# Display_Segmental_LCD118x1_DF700543-05_B.net
KiCad netlist of a schematic drawn in Altium Designer
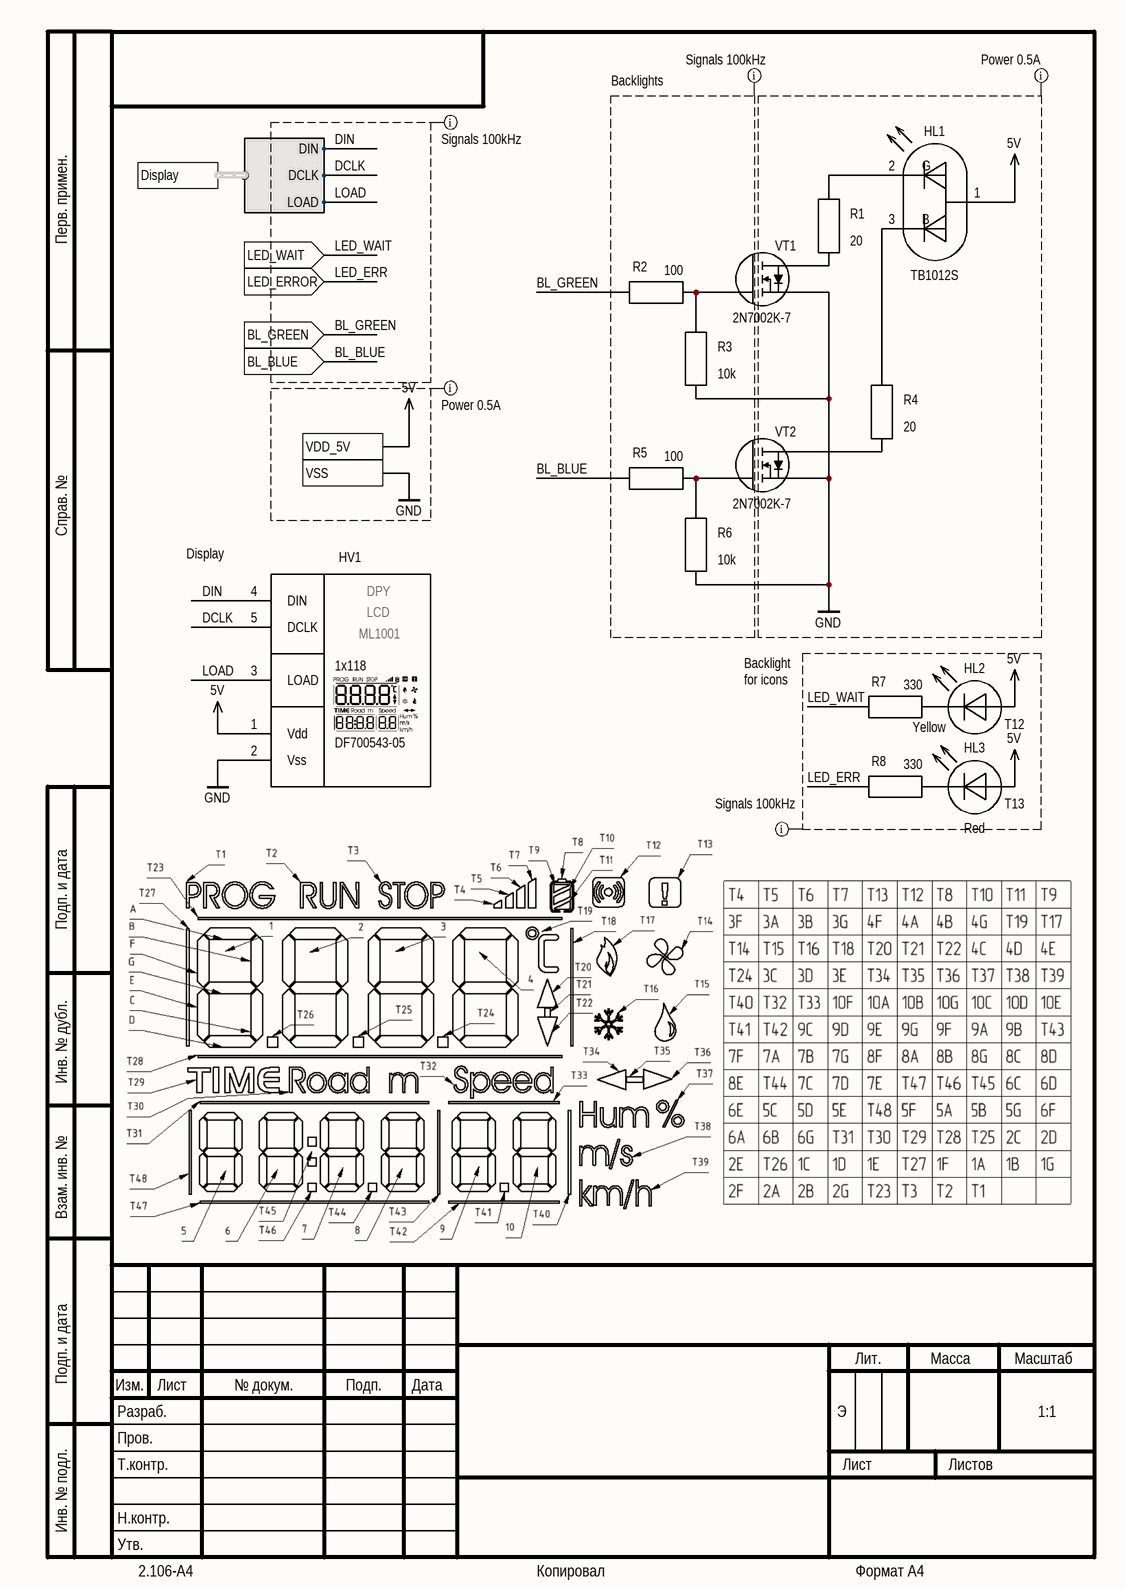
[diagram p0: Display Segmental LCD118x1 DF700543-05 Backlight TB1012S 1608.SchDoc]

(export (version "E")
  (design (tool "Eeschema 10.0.6"))
  (components
    (comp (ref "HL1")
      (value "TB1012S")
      (footprint "DISP BKL LED TB1012S")
      (description "Display Backlight LED GB CA")
      (libsource (lib "Displays") (part "TB1012S"))
    )
    (comp (ref "HL2")
      (value "Yellow")
      (footprint "LEDD3TBN")
      (description "LED Yellow TH D3mm")
      (fields (field (name "MANUFACTURER") "Lite-On"))
      (libsource (lib "LED") (part "LTL-4251"))
    )
    (comp (ref "HL3")
      (value "Red")
      (footprint "LEDD3TBN")
      (description "LED Red TH D3mm")
      (fields (field (name "MANUFACTURER") "Lite-On"))
      (libsource (lib "LED") (part "LTL-4211"))
    )
    (comp (ref "HV1")
      (value "DF700543-05")
      (footprint "DISP SEG LCD128 DF700543-05")
      (description "Display Segmental LCD128 Special")
      (libsource (lib "Displays") (part "DF700543-05"))
    )
    (comp (ref "R1")
      (value "20")
      (footprint "RESC3225N")
      (description "RESC 20 1210(3225)")
      (fields (field (name "MANUFACTURER") "Yageo") (field (name "TOLERANCE") "±1%"))
      (libsource (lib "Resistors Ceramic SMD") (part "RC1210JR-0720RL"))
    )
    (comp (ref "R2")
      (value "100")
      (footprint "RESC1608N")
      (description "RESC 100 0603(1608)")
      (fields (field (name "MANUFACTURER") "Yageo") (field (name "TOLERANCE") "±5%"))
      (libsource (lib "Resistors Ceramic SMD") (part "RC0603JR-07100RL"))
    )
    (comp (ref "R3")
      (value "10k")
      (footprint "RESC1608N")
      (description "RESC 10k 0603(1608)")
      (fields (field (name "MANUFACTURER") "Yageo") (field (name "TOLERANCE") "±5%"))
      (libsource (lib "Resistors Ceramic SMD") (part "RC0603JR-0710KL"))
    )
    (comp (ref "R4")
      (value "20")
      (footprint "RESC3225N")
      (description "RESC 20 1210(3225)")
      (fields (field (name "MANUFACTURER") "Yageo") (field (name "TOLERANCE") "±1%"))
      (libsource (lib "Resistors Ceramic SMD") (part "RC1210JR-0720RL"))
    )
    (comp (ref "R5")
      (value "100")
      (footprint "RESC1608N")
      (description "RESC 100 0603(1608)")
      (fields (field (name "MANUFACTURER") "Yageo") (field (name "TOLERANCE") "±5%"))
      (libsource (lib "Resistors Ceramic SMD") (part "RC0603JR-07100RL"))
    )
    (comp (ref "R6")
      (value "10k")
      (footprint "RESC1608N")
      (description "RESC 10k 0603(1608)")
      (fields (field (name "MANUFACTURER") "Yageo") (field (name "TOLERANCE") "±5%"))
      (libsource (lib "Resistors Ceramic SMD") (part "RC0603JR-0710KL"))
    )
    (comp (ref "R7")
      (value "330")
      (footprint "RESC1608N")
      (description "RESC 330 0603(1608)")
      (fields (field (name "MANUFACTURER") "Yageo") (field (name "TOLERANCE") "±5%"))
      (libsource (lib "Resistors Ceramic SMD") (part "RC0603JR-07330RL"))
    )
    (comp (ref "R8")
      (value "330")
      (footprint "RESC1608N")
      (description "RESC 330 0603(1608)")
      (fields (field (name "MANUFACTURER") "Yageo") (field (name "TOLERANCE") "±5%"))
      (libsource (lib "Resistors Ceramic SMD") (part "RC0603JR-07330RL"))
    )
    (comp (ref "VT1")
      (value "2N7002K-7")
      (footprint "SOT-23-3N")
      (description "MOSFET N 0.38A 60V")
      (fields (field (name "MANUFACTURER") "Diodes Incorporated"))
      (libsource (lib "Transistors") (part "2N7002K-7"))
    )
    (comp (ref "VT2")
      (value "2N7002K-7")
      (footprint "SOT-23-3N")
      (description "MOSFET N 0.38A 60V")
      (fields (field (name "MANUFACTURER") "Diodes Incorporated"))
      (libsource (lib "Transistors") (part "2N7002K-7"))
    )
  )
  (nets
    (net (code "2") (name "/BL_BLUE") (class "Default")
      (node (ref "R5") (pin "1") (pinfunction "1_1") (pintype "passive"))
    )
    (net (code "3") (name "/BL_GREEN") (class "Default")
      (node (ref "R2") (pin "1") (pinfunction "1_1") (pintype "passive"))
    )
    (net (code "4") (name "/DCLK") (class "Default")
      (node (ref "HV1") (pin "5") (pinfunction "DCLK_5") (pintype "passive"))
    )
    (net (code "5") (name "/DIN") (class "Default")
      (node (ref "HV1") (pin "4") (pinfunction "DIN_4") (pintype "passive"))
    )
    (net (code "6") (name "/LED_ERR") (class "Default")
      (node (ref "R8") (pin "1") (pinfunction "1_1") (pintype "passive"))
    )
    (net (code "7") (name "/LED_WAIT") (class "Default")
      (node (ref "R7") (pin "1") (pinfunction "1_1") (pintype "passive"))
    )
    (net (code "8") (name "/LOAD") (class "Default")
      (node (ref "HV1") (pin "3") (pinfunction "LOAD_3") (pintype "passive"))
    )
    (net (code "10") (name "5V") (class "Default")
      (node (ref "HL1") (pin "1") (pinfunction "CA_1") (pintype "passive"))
      (node (ref "HL2") (pin "1") (pinfunction "Anode_1") (pintype "passive"))
      (node (ref "HL3") (pin "1") (pinfunction "Anode_1") (pintype "passive"))
      (node (ref "HV1") (pin "1") (pinfunction "Vdd_1") (pintype "passive"))
    )
    (net (code "11") (name "GND") (class "Default")
      (node (ref "HV1") (pin "2") (pinfunction "Vss_2") (pintype "passive"))
      (node (ref "R3") (pin "2") (pinfunction "2_2") (pintype "passive"))
      (node (ref "R6") (pin "2") (pinfunction "2_2") (pintype "passive"))
      (node (ref "VT1") (pin "2") (pinfunction "Source_2") (pintype "passive"))
      (node (ref "VT2") (pin "2") (pinfunction "Source_2") (pintype "passive"))
    )
    (net (code "12") (name "Net-(HL1-BLUE)") (class "Default")
      (node (ref "HL1") (pin "3") (pinfunction "BLUE_3") (pintype "passive"))
      (node (ref "R4") (pin "1") (pinfunction "1_1") (pintype "passive"))
    )
    (net (code "13") (name "Net-(HL1-GREEN)") (class "Default")
      (node (ref "HL1") (pin "2") (pinfunction "GREEN_2") (pintype "passive"))
      (node (ref "R1") (pin "1") (pinfunction "1_1") (pintype "passive"))
    )
    (net (code "14") (name "Net-(HL2-Cathode)") (class "Default")
      (node (ref "HL2") (pin "2") (pinfunction "Cathode_2") (pintype "passive"))
      (node (ref "R7") (pin "2") (pinfunction "2_2") (pintype "passive"))
    )
    (net (code "15") (name "Net-(HL3-Cathode)") (class "Default")
      (node (ref "HL3") (pin "2") (pinfunction "Cathode_2") (pintype "passive"))
      (node (ref "R8") (pin "2") (pinfunction "2_2") (pintype "passive"))
    )
    (net (code "16") (name "Net-(VT1-Drain)") (class "Default")
      (node (ref "R1") (pin "2") (pinfunction "2_2") (pintype "passive"))
      (node (ref "VT1") (pin "3") (pinfunction "Drain_3") (pintype "passive"))
    )
    (net (code "17") (name "Net-(VT1-Gate)") (class "Default")
      (node (ref "R2") (pin "2") (pinfunction "2_2") (pintype "passive"))
      (node (ref "R3") (pin "1") (pinfunction "1_1") (pintype "passive"))
      (node (ref "VT1") (pin "1") (pinfunction "Gate_1") (pintype "passive"))
    )
    (net (code "18") (name "Net-(VT2-Drain)") (class "Default")
      (node (ref "R4") (pin "2") (pinfunction "2_2") (pintype "passive"))
      (node (ref "VT2") (pin "3") (pinfunction "Drain_3") (pintype "passive"))
    )
    (net (code "19") (name "Net-(VT2-Gate)") (class "Default")
      (node (ref "R5") (pin "2") (pinfunction "2_2") (pintype "passive"))
      (node (ref "R6") (pin "1") (pinfunction "1_1") (pintype "passive"))
      (node (ref "VT2") (pin "1") (pinfunction "Gate_1") (pintype "passive"))
    )
  )
)
